# DM3370_Power.net
KiCad netlist of a schematic drawn in Altium Designer
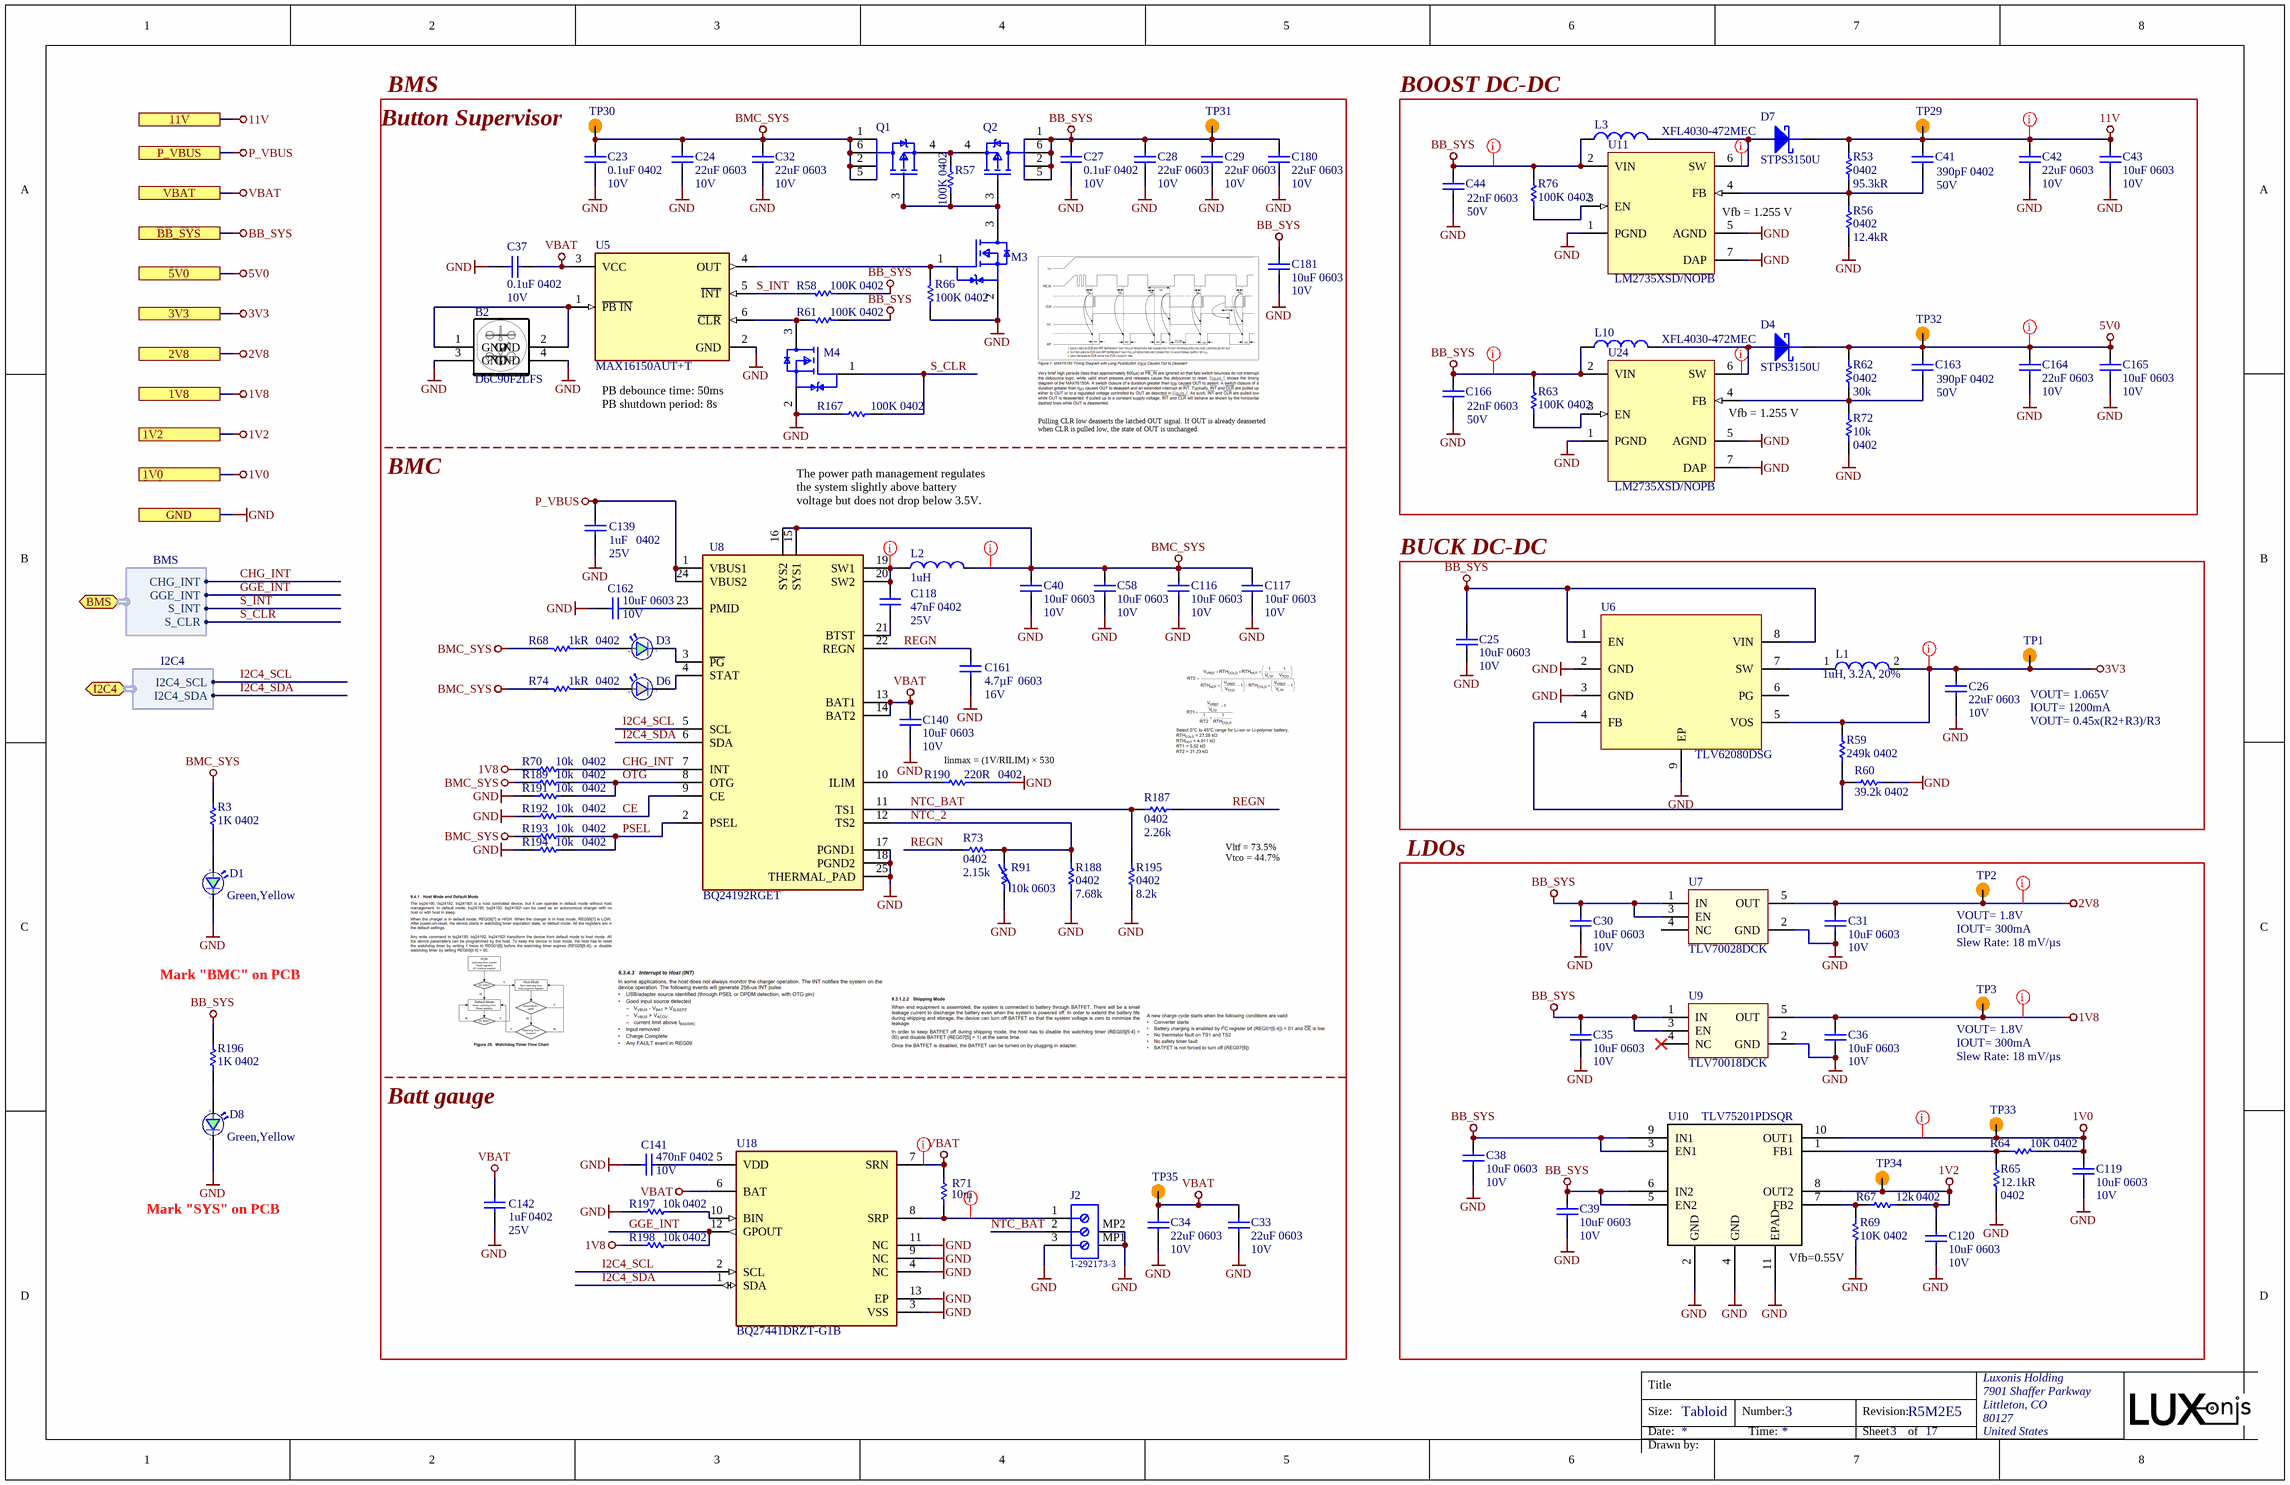
[diagram p0: DM3370_Power.SchDoc]

(export (version "E")
  (design (tool "Eeschema 10.0.6"))
  (components
    (comp (ref "B2")
      (value "D6C90F2LFS")
      (footprint "CON_B_BW2099_SoM_DF40HC-3.0-100DS-0.4V_minpad")
      (libsource (lib "Luxonis LLC") (part "D6C90"))
    )
    (comp (ref "C23")
      (value "0.1uF 0402")
      (footprint "CAP_Altium_Vault_Generic:CAPC0402(1005)70_L")
      (description "CAP CER 0.1UF 10V X7R 0402 5%")
      (fields (field (name "TOLERANCE") "5%") (field (name "VOLTAGE RATING") "10V"))
      (libsource (lib "LuxonisMaster") (part "GRM155R71A104JA01D"))
    )
    (comp (ref "C24")
      (value "22uF 0603")
      (footprint "CAP_Altium_Vault_Generic:CAPC0603(1608)100_L")
      (description "CAP CER 22UF 10V X5R 0603 20%")
      (fields (field (name "TOLERANCE") "20%") (field (name "VOLTAGE RATING") "10V"))
      (libsource (lib "LuxonisMaster") (part "GRM188R61A226ME15D"))
    )
    (comp (ref "C25")
      (value "10uF 0603")
      (footprint "CAP_Altium_Vault_Generic:CAPC0603(1608)100_L")
      (description "CAP CER 10UF 10V X5R 0603 20%")
      (fields (field (name "TOLERANCE") "20%") (field (name "VOLTAGE RATING") "10V"))
      (libsource (lib "LuxonisMaster") (part "GRM188R61A106ME69D"))
    )
    (comp (ref "C26")
      (value "22uF 0603")
      (footprint "CAP_Altium_Vault_Generic:CAPC0603(1608)100_L")
      (description "CAP CER 22UF 10V X5R 0603 20%")
      (fields (field (name "TOLERANCE") "20%") (field (name "VOLTAGE RATING") "10V"))
      (libsource (lib "LuxonisMaster") (part "GRM188R61A226ME15D"))
    )
    (comp (ref "C27")
      (value "0.1uF 0402")
      (footprint "CAP_Altium_Vault_Generic:CAPC0402(1005)70_L")
      (description "CAP CER 0.1UF 10V X7R 0402 5%")
      (fields (field (name "TOLERANCE") "5%") (field (name "VOLTAGE RATING") "10V"))
      (libsource (lib "LuxonisMaster") (part "GRM155R71A104JA01D"))
    )
    (comp (ref "C28")
      (value "22uF 0603")
      (footprint "CAP_Altium_Vault_Generic:CAPC0603(1608)100_L")
      (description "CAP CER 22UF 10V X5R 0603 20%")
      (fields (field (name "TOLERANCE") "20%") (field (name "VOLTAGE RATING") "10V"))
      (libsource (lib "LuxonisMaster") (part "GRM188R61A226ME15D"))
    )
    (comp (ref "C29")
      (value "22uF 0603")
      (footprint "CAP_Altium_Vault_Generic:CAPC0603(1608)100_L")
      (description "CAP CER 22UF 10V X5R 0603 20%")
      (fields (field (name "TOLERANCE") "20%") (field (name "VOLTAGE RATING") "10V"))
      (libsource (lib "LuxonisMaster") (part "GRM188R61A226ME15D"))
    )
    (comp (ref "C30")
      (value "10uF 0603")
      (footprint "CAP_Altium_Vault_Generic:CAPC0603(1608)100_L")
      (description "CAP CER 10UF 10V X5R 0603 20%")
      (fields (field (name "TOLERANCE") "20%") (field (name "VOLTAGE RATING") "10V"))
      (libsource (lib "LuxonisMaster") (part "GRM188R61A106ME69D"))
    )
    (comp (ref "C31")
      (value "10uF 0603")
      (footprint "CAP_Altium_Vault_Generic:CAPC0603(1608)100_L")
      (description "CAP CER 10UF 10V X5R 0603 20%")
      (fields (field (name "TOLERANCE") "20%") (field (name "VOLTAGE RATING") "10V"))
      (libsource (lib "LuxonisMaster") (part "GRM188R61A106ME69D"))
    )
    (comp (ref "C32")
      (value "22uF 0603")
      (footprint "CAP_Altium_Vault_Generic:CAPC0603(1608)100_L")
      (description "CAP CER 22UF 10V X5R 0603 20%")
      (fields (field (name "TOLERANCE") "20%") (field (name "VOLTAGE RATING") "10V"))
      (libsource (lib "LuxonisMaster") (part "GRM188R61A226ME15D"))
    )
    (comp (ref "C33")
      (value "22uF 0603")
      (footprint "CAP_Altium_Vault_Generic:CAPC0603(1608)100_L")
      (description "CAP CER 22UF 10V X5R 0603 20%")
      (fields (field (name "TOLERANCE") "20%") (field (name "VOLTAGE RATING") "10V"))
      (libsource (lib "LuxonisMaster") (part "GRM188R61A226ME15D"))
    )
    (comp (ref "C34")
      (value "22uF 0603")
      (footprint "CAP_Altium_Vault_Generic:CAPC0603(1608)100_L")
      (description "CAP CER 22UF 10V X5R 0603 20%")
      (fields (field (name "TOLERANCE") "20%") (field (name "VOLTAGE RATING") "10V"))
      (libsource (lib "LuxonisMaster") (part "GRM188R61A226ME15D"))
    )
    (comp (ref "C35")
      (value "10uF 0603")
      (footprint "CAP_Altium_Vault_Generic:CAPC0603(1608)100_L")
      (description "CAP CER 10UF 10V X5R 0603 20%")
      (fields (field (name "TOLERANCE") "20%") (field (name "VOLTAGE RATING") "10V"))
      (libsource (lib "LuxonisMaster") (part "GRM188R61A106ME69D"))
    )
    (comp (ref "C36")
      (value "10uF 0603")
      (footprint "CAP_Altium_Vault_Generic:CAPC0603(1608)100_L")
      (description "CAP CER 10UF 10V X5R 0603 20%")
      (fields (field (name "TOLERANCE") "20%") (field (name "VOLTAGE RATING") "10V"))
      (libsource (lib "LuxonisMaster") (part "GRM188R61A106ME69D"))
    )
    (comp (ref "C37")
      (value "0.1uF 0402")
      (footprint "CAP_Altium_Vault_Generic:CAPC0402(1005)70_L")
      (description "CAP CER 0.1UF 10V X7R 0402 5%")
      (fields (field (name "TOLERANCE") "5%") (field (name "VOLTAGE RATING") "10V"))
      (libsource (lib "LuxonisMaster") (part "GRM155R71A104JA01D"))
    )
    (comp (ref "C38")
      (value "10uF 0603")
      (footprint "CAP_Altium_Vault_Generic:CAPC0603(1608)100_L")
      (description "CAP CER 10UF 10V X5R 0603 20%")
      (fields (field (name "TOLERANCE") "20%") (field (name "VOLTAGE RATING") "10V"))
      (libsource (lib "LuxonisMaster") (part "GRM188R61A106ME69D"))
    )
    (comp (ref "C39")
      (value "10uF 0603")
      (footprint "CAP_Altium_Vault_Generic:CAPC0603(1608)100_L")
      (description "CAP CER 10UF 10V X5R 0603 20%")
      (fields (field (name "TOLERANCE") "20%") (field (name "VOLTAGE RATING") "10V"))
      (libsource (lib "LuxonisMaster") (part "GRM188R61A106ME69D"))
    )
    (comp (ref "C40")
      (value "10uF 0603")
      (footprint "CAP_Altium_Vault_Generic:CAPC0603(1608)100_L")
      (description "CAP CER 10UF 10V X5R 0603 20%")
      (fields (field (name "TOLERANCE") "20%") (field (name "VOLTAGE RATING") "10V"))
      (libsource (lib "LuxonisMaster") (part "GRM188R61A106ME69D"))
    )
    (comp (ref "C41")
      (value "GRM1555C1H391JA01J")
      (footprint "CAPC0402(1005)60_L")
      (description "CAP CER 390PF 50V C0G 0402")
      (fields
        (field (name "RATED DC VOLTAGE (URDC)") "50V")
        (field (name "CAPACITANCE") "390pF")
        (field (name "SIZE CODE") "0402")
      )
      (libsource (lib "Luxonis LLC") (part "LLL153C70G474ME17E"))
    )
    (comp (ref "C42")
      (value "22uF 0603")
      (footprint "CAP_Altium_Vault_Generic:CAPC0603(1608)100_L")
      (description "CAP CER 22UF 10V X5R 0603 20%")
      (fields (field (name "TOLERANCE") "20%") (field (name "VOLTAGE RATING") "10V"))
      (libsource (lib "LuxonisMaster") (part "GRM188R61A226ME15D"))
    )
    (comp (ref "C43")
      (value "10uF 0603")
      (footprint "CAP_Altium_Vault_Generic:CAPC0603(1608)100_L")
      (description "CAP CER 10UF 10V X5R 0603 20%")
      (fields (field (name "TOLERANCE") "20%") (field (name "VOLTAGE RATING") "10V"))
      (libsource (lib "LuxonisMaster") (part "GRM188R61A106ME69D"))
    )
    (comp (ref "C44")
      (value "C0603C223K5RACTU")
      (footprint "CAPC0603(1608)100_L")
      (description "CAP CER 0.022UF 50V X7R 0603")
      (fields
        (field (name "VOLTAGE RATING") "50V")
        (field (name "TOLERANCE") "10%")
        (field (name "CASE CODE (IMPERIAL)") "0603")
        (field (name "VOLTAGE") "50V")
        (field (name "CAPACITANCE") "22nF")
      )
      (libsource (lib "Luxonis LLC") (part "LLL153C70G474ME17E"))
    )
    (comp (ref "C58")
      (value "10uF 0603")
      (footprint "CAP_Altium_Vault_Generic:CAPC0603(1608)100_L")
      (description "CAP CER 10UF 10V X5R 0603 20%")
      (fields (field (name "TOLERANCE") "20%") (field (name "VOLTAGE RATING") "10V"))
      (libsource (lib "LuxonisMaster") (part "GRM188R61A106ME69D"))
    )
    (comp (ref "C116")
      (value "10uF 0603")
      (footprint "CAP_Altium_Vault_Generic:CAPC0603(1608)100_L")
      (description "CAP CER 10UF 10V X5R 0603 20%")
      (fields (field (name "TOLERANCE") "20%") (field (name "VOLTAGE RATING") "10V"))
      (libsource (lib "LuxonisMaster") (part "GRM188R61A106ME69D"))
    )
    (comp (ref "C117")
      (value "10uF 0603")
      (footprint "CAP_Altium_Vault_Generic:CAPC0603(1608)100_L")
      (description "CAP CER 10UF 10V X5R 0603 20%")
      (fields (field (name "TOLERANCE") "20%") (field (name "VOLTAGE RATING") "10V"))
      (libsource (lib "LuxonisMaster") (part "GRM188R61A106ME69D"))
    )
    (comp (ref "C118")
      (value "GRM155R71E473KA88D")
      (footprint "CAPC0402(1005)70_L")
      (description "CAP CER 0.047UF 25V X7R 0402 10%")
      (fields
        (field (name "CASE CODE (IMPERIAL)") "0402")
        (field (name "MANUFACTURER") "Murata")
        (field (name "CAPACITANCE") "47nF")
        (field (name "TOLERANCE") "10%")
        (field (name "VOLTAGE") "25V")
      )
      (libsource (lib "Luxonis LLC") (part "LLL153C70G474ME17E"))
    )
    (comp (ref "C119")
      (value "10uF 0603")
      (footprint "CAP_Altium_Vault_Generic:CAPC0603(1608)100_L")
      (description "CAP CER 10UF 10V X5R 0603 20%")
      (fields (field (name "TOLERANCE") "20%") (field (name "VOLTAGE RATING") "10V"))
      (libsource (lib "LuxonisMaster") (part "GRM188R61A106ME69D"))
    )
    (comp (ref "C120")
      (value "10uF 0603")
      (footprint "CAP_Altium_Vault_Generic:CAPC0603(1608)100_L")
      (description "CAP CER 10UF 10V X5R 0603 20%")
      (fields (field (name "TOLERANCE") "20%") (field (name "VOLTAGE RATING") "10V"))
      (libsource (lib "LuxonisMaster") (part "GRM188R61A106ME69D"))
    )
    (comp (ref "C139")
      (value "GRM155R61E105KA12D")
      (footprint "CAPC0402(1005)70_L")
      (description "CAP CER 1UF 25V X5R 0402 10%")
      (fields
        (field (name "CASE CODE (IMPERIAL)") "0402")
        (field (name "VOLTAGE") "25V")
        (field (name "CAPACITANCE") "1uF")
        (field (name "TOLERANCE") "10%")
      )
      (libsource (lib "Luxonis LLC") (part "GRM188R61C475KAAJD"))
    )
    (comp (ref "C140")
      (value "10uF 0603")
      (footprint "CAP_Altium_Vault_Generic:CAPC0603(1608)100_L")
      (description "CAP CER 10UF 10V X5R 0603 20%")
      (fields (field (name "TOLERANCE") "20%") (field (name "VOLTAGE RATING") "10V"))
      (libsource (lib "LuxonisMaster") (part "GRM188R61A106ME69D"))
    )
    (comp (ref "C141")
      (value "GRM155R61A474KE15D")
      (footprint "CAPC0402(1005)70_L")
      (description "CAP CER 0.47UF 10V X5R 0402")
      (fields
        (field (name "VOLTAGE RATING") "10V")
        (field (name "CAPACITANCE") "470nF")
        (field (name "TOLERANCE") "10%")
        (field (name "CASE/PACKAGE") "0402")
        (field (name "VOLTAGE") "10V")
      )
      (libsource (lib "Luxonis LLC") (part "LLL153C70G474ME17E"))
    )
    (comp (ref "C142")
      (value "GRM155R61E105KA12D")
      (footprint "CAPC0402(1005)70_L")
      (description "CAP CER 1UF 25V X5R 0402 10%")
      (fields
        (field (name "CASE CODE (IMPERIAL)") "0402")
        (field (name "VOLTAGE") "25V")
        (field (name "CAPACITANCE") "1uF")
        (field (name "TOLERANCE") "10%")
      )
      (libsource (lib "Luxonis LLC") (part "GRM188R61C475KAAJD"))
    )
    (comp (ref "C161")
      (value "4.7µF")
      (footprint "CAPC0603(1608)100_L")
      (description "CAP CER 4.7UF 16V X5R 0603 10%")
      (fields
        (field (name "VOLTAGE RATING") "16V")
        (field (name "TOLERANCE") "10%")
        (field (name "CASE/PACKAGE") "0603")
        (field (name "Comment") "GRM188R61C475KAAJD")
      )
      (libsource (lib "Luxonis LLC") (part "LLL153C70G474ME17E"))
    )
    (comp (ref "C162")
      (value "10uF 0603")
      (footprint "CAP_Altium_Vault_Generic:CAPC0603(1608)100_L")
      (description "CAP CER 10UF 10V X5R 0603 20%")
      (fields (field (name "TOLERANCE") "20%") (field (name "VOLTAGE RATING") "10V"))
      (libsource (lib "LuxonisMaster") (part "GRM188R61A106ME69D"))
    )
    (comp (ref "C163")
      (value "GRM1555C1H391JA01J")
      (footprint "CAPC0402(1005)60_L")
      (description "CAP CER 390PF 50V C0G 0402")
      (fields
        (field (name "RATED DC VOLTAGE (URDC)") "50V")
        (field (name "CAPACITANCE") "390pF")
        (field (name "SIZE CODE") "0402")
      )
      (libsource (lib "Luxonis LLC") (part "LLL153C70G474ME17E"))
    )
    (comp (ref "C164")
      (value "22uF 0603")
      (footprint "CAP_Altium_Vault_Generic:CAPC0603(1608)100_L")
      (description "CAP CER 22UF 10V X5R 0603 20%")
      (fields (field (name "TOLERANCE") "20%") (field (name "VOLTAGE RATING") "10V"))
      (libsource (lib "LuxonisMaster") (part "GRM188R61A226ME15D"))
    )
    (comp (ref "C165")
      (value "10uF 0603")
      (footprint "CAP_Altium_Vault_Generic:CAPC0603(1608)100_L")
      (description "CAP CER 10UF 10V X5R 0603 20%")
      (fields (field (name "TOLERANCE") "20%") (field (name "VOLTAGE RATING") "10V"))
      (libsource (lib "LuxonisMaster") (part "GRM188R61A106ME69D"))
    )
    (comp (ref "C166")
      (value "C0603C223K5RACTU")
      (footprint "CAPC0603(1608)100_L")
      (description "CAP CER 0.022UF 50V X7R 0603")
      (fields
        (field (name "VOLTAGE RATING") "50V")
        (field (name "TOLERANCE") "10%")
        (field (name "CASE CODE (IMPERIAL)") "0603")
        (field (name "VOLTAGE") "50V")
        (field (name "CAPACITANCE") "22nF")
      )
      (libsource (lib "Luxonis LLC") (part "LLL153C70G474ME17E"))
    )
    (comp (ref "C180")
      (value "22uF 0603")
      (footprint "CAP_Altium_Vault_Generic:CAPC0603(1608)100_L")
      (description "CAP CER 22UF 10V X5R 0603 20%")
      (fields (field (name "TOLERANCE") "20%") (field (name "VOLTAGE RATING") "10V"))
      (libsource (lib "LuxonisMaster") (part "GRM188R61A226ME15D"))
    )
    (comp (ref "C181")
      (value "10uF 0603")
      (footprint "CAP_Altium_Vault_Generic:CAPC0603(1608)100_L")
      (description "CAP CER 10UF 10V X5R 0603 20%")
      (fields (field (name "TOLERANCE") "20%") (field (name "VOLTAGE RATING") "10V"))
      (libsource (lib "LuxonisMaster") (part "GRM188R61A106ME69D"))
    )
    (comp (ref "D1")
      (value "SML-D12M8WT86")
      (footprint "SML_D1xx8W")
      (description "LED GREEN DIFFUSED 0603 SMD Green 572nm LED Indication - Discrete 2.2V 0603 (1608 Metric)")
      (fields (field (name "COLOR") "Green,Yellow"))
      (libsource (lib "Luxonis LLC") (part "SML-D12M8WT86"))
    )
    (comp (ref "D3")
      (value "SML-D12M8WT86")
      (footprint "SML_D1xx8W")
      (description "LED GREEN DIFFUSED 0603 SMD Green 572nm LED Indication - Discrete 2.2V 0603 (1608 Metric)")
      (fields (field (name "MANUFACTURER") "Rohm"))
      (libsource (lib "Luxonis LLC") (part "SML-D12M8WT86"))
    )
    (comp (ref "D4")
      (value "STPS3150U")
      (footprint "FP-SMB-MFG")
      (description "DIODE SCHOTTKY 150V 3A SMB")
      (fields
        (field (name "OCTOPART") "https://octopart.com/stps3150u-stmicroelectronics-39552976")
        (field (name "MANUFACTURER") "STMicroelectronics")
      )
      (libsource (lib "LuxonisMaster") (part "STPS3150U"))
    )
    (comp (ref "D6")
      (value "SML-D12D8WT86")
      (footprint "SML_D1xx8W")
      (description "LED ORANGE DIFFUSED 0603 SMD Orange 605nm LED Indication - Discrete 2.2V 0603 (1608 Metric)")
      (libsource (lib "Luxonis LLC") (part "SML-D12D8WT86"))
    )
    (comp (ref "D7")
      (value "STPS3150U")
      (footprint "FP-SMB-MFG")
      (description "DIODE SCHOTTKY 150V 3A SMB")
      (fields
        (field (name "OCTOPART") "https://octopart.com/stps3150u-stmicroelectronics-39552976")
        (field (name "MANUFACTURER") "STMicroelectronics")
      )
      (libsource (lib "LuxonisMaster") (part "STPS3150U"))
    )
    (comp (ref "D8")
      (value "SML-D12M8WT86")
      (footprint "SML_D1xx8W")
      (description "LED GREEN DIFFUSED 0603 SMD Green 572nm LED Indication - Discrete 2.2V 0603 (1608 Metric)")
      (fields (field (name "COLOR") "Green,Yellow"))
      (libsource (lib "Luxonis LLC") (part "SML-D12M8WT86"))
    )
    (comp (ref "J2")
      (value "1-292173-3")
      (footprint "1-292173-3")
      (description "Board Connector, 3 Contact(s), 1 Row(s), Male, Right Angle, Surface Mount Terminal")
      (libsource (lib "Luxonis LLC") (part "1-292173-3"))
    )
    (comp (ref "L1")
      (value "1uH, 3.2A, 20%")
      (footprint "LuxonisMaster:DFE252012P-1R0M=P2")
      (description "FIXED IND 1UH 3.2A 42 MOHM SMD")
      (fields
        (field (name "MANUFACTURER") "Murata")
        (field (name "MANUFACTURER PART NUMBER") "DFE252012P-1R0M=P2")
      )
      (libsource (lib "LuxonisMaster") (part "DFE252012P-1R0M=P2"))
    )
    (comp (ref "L2")
      (value "XFL4020-102MEC")
      (footprint "COIL-XFL4020_V")
      (description "Fixed Inductors 11A 11.9mR XFL4020")
      (fields
        (field (name "TOLERANCE") "20%")
        (field (name "INDUCTANCE") "1uH")
        (field (name "AVAILABLE PREVIEW IMAGES") "2D")
      )
      (libsource (lib "Luxonis LLC") (part "XFL4030-472MEC"))
    )
    (comp (ref "L3")
      (value "XFL4030-472MEC")
      (footprint "XFL4030-472MEC-MFG")
      (description "Fixed Inductors 5.7A 25mR XFL4030")
      (libsource (lib "LuxonisMaster") (part "XFL4030-472MEC"))
    )
    (comp (ref "L10")
      (value "XFL4030-472MEC")
      (footprint "XFL4030-472MEC-MFG")
      (description "Fixed Inductors 5.7A 25mR XFL4030")
      (libsource (lib "LuxonisMaster") (part "XFL4030-472MEC"))
    )
    (comp (ref "M3")
      (value "RE1C002UNTCL")
      (footprint "LuxonisMaster:RE1C002UNTCL")
      (description "MOSFET N-CH 20V 0.2A EMT3")
      (libsource (lib "LuxonisMaster") (part "RE1C002UNTCL"))
    )
    (comp (ref "M4")
      (value "RE1C002UNTCL")
      (footprint "LuxonisMaster:RE1C002UNTCL")
      (description "MOSFET N-CH 20V 0.2A EMT3")
      (libsource (lib "LuxonisMaster") (part "RE1C002UNTCL"))
    )
    (comp (ref "Q1")
      (value "IRLTS2242TRPBF")
      (footprint "TSOP-6-MFG")
      (description "MOSFET P-CH 20V 6.9A 6TSOP")
      (libsource (lib "Luxonis LLC") (part "IRLTS2242TRPBF"))
    )
    (comp (ref "Q2")
      (value "IRLTS2242TRPBF")
      (footprint "TSOP-6-MFG")
      (description "MOSFET P-CH 20V 6.9A 6TSOP")
      (libsource (lib "Luxonis LLC") (part "IRLTS2242TRPBF"))
    )
    (comp (ref "R3")
      (value "1K 0402")
      (footprint "RES_Altium_Vault_Generic:RESC0402(1005)_L")
      (fields (field (name "TOLERANCE") "1%"))
      (libsource (lib "LuxonisMaster") (part "RC0402FR-071KL"))
    )
    (comp (ref "R53")
      (value "CRCW040295K3FKED")
      (footprint "RESC0402(1005)_L")
      (description "RES SMD 95.3K OHM 1% 1/16W 0402")
      (fields
        (field (name "CASE CODE (IMPERIAL)") "0402")
        (field (name "RESISTANCE") "95.3kR")
        (field (name "TOLERANCE") "1%")
      )
      (libsource (lib "Luxonis LLC") (part "CR0402-FX-2492GLF"))
    )
    (comp (ref "R56")
      (value "RC0402FR-0712K4L")
      (footprint "RESC0402(1005)_L")
      (description "RES SMD 12.4K OHM 1% 1/16W 0402")
      (fields
        (field (name "CASE CODE (IMPERIAL)") "0402")
        (field (name "TOLERANCE") "1%")
        (field (name "RESISTANCE") "12.4kR")
      )
      (libsource (lib "Luxonis LLC") (part "CR0402-FX-2492GLF"))
    )
    (comp (ref "R57")
      (value "100K 0402")
      (footprint "RES_Altium_Vault_Generic:RESC0402(1005)_L")
      (description "RES SMD 100K OHM 1% 1/16W 0402")
      (fields (field (name "TOLERANCE") "1%"))
      (libsource (lib "LuxonisMaster") (part "RC0402FR-07100KL"))
    )
    (comp (ref "R58")
      (value "100K 0402")
      (footprint "RES_Altium_Vault_Generic:RESC0402(1005)_L")
      (description "RES SMD 100K OHM 1% 1/16W 0402")
      (fields (field (name "TOLERANCE") "1%"))
      (libsource (lib "LuxonisMaster") (part "RC0402FR-07100KL"))
    )
    (comp (ref "R59")
      (value "249k 0402")
      (footprint "RES_Altium_Vault_Generic:RESC0402(1005)_L")
      (description "RES SMD 249K OHM 1% 1/16W 0402")
      (fields (field (name "TOLERANCE") "1%"))
      (libsource (lib "LuxonisMaster") (part "CRCW0402249KFKED"))
    )
    (comp (ref "R60")
      (value "39.2k 0402")
      (footprint "RES_Altium_Vault_Generic:RESC0402(1005)_L")
      (description "RES SMD 39.2K OHM 1% 1/16W 0402")
      (fields (field (name "TOLERANCE") "1%"))
      (libsource (lib "LuxonisMaster") (part "CRCW040239K2FKED"))
    )
    (comp (ref "R61")
      (value "100K 0402")
      (footprint "RES_Altium_Vault_Generic:RESC0402(1005)_L")
      (description "RES SMD 100K OHM 1% 1/16W 0402")
      (fields (field (name "TOLERANCE") "1%"))
      (libsource (lib "LuxonisMaster") (part "RC0402FR-07100KL"))
    )
    (comp (ref "R62")
      (value "30k")
      (footprint "RESC0402(1005)_L")
      (description "RES SMD 30K OHM 1% 1/16W 0402")
      (fields
        (field (name "CASE/PACKAGE") "0402")
        (field (name "TOLERANCE") "1%")
        (field (name "Comment") "RC0402FR-0730KL")
      )
      (libsource (lib "Luxonis LLC") (part "Default resistor symbol"))
    )
    (comp (ref "R63")
      (value "100K 0402")
      (footprint "RES_Altium_Vault_Generic:RESC0402(1005)_L")
      (description "RES SMD 100K OHM 1% 1/16W 0402")
      (fields (field (name "TOLERANCE") "1%"))
      (libsource (lib "LuxonisMaster") (part "RC0402FR-07100KL"))
    )
    (comp (ref "R64")
      (value "10K 0402")
      (footprint "RES_Altium_Vault_Generic:RESC0402(1005)_L")
      (fields (field (name "TOLERANCE") "1%"))
      (libsource (lib "LuxonisMaster") (part "RC0402FR-1310KL"))
    )
    (comp (ref "R65")
      (value "RC0402FR-0712K1L")
      (footprint "RESC0402(1005)_L")
      (description "RES SMD 12.1K OHM 1% 1/16W 0402")
      (fields
        (field (name "RESISTANCE") "12.1kR")
        (field (name "SIZE CODE") "0402")
        (field (name "TOLERANCE") "1%")
      )
      (libsource (lib "Luxonis LLC") (part "CR1206-FX-10R0ELF"))
    )
    (comp (ref "R66")
      (value "100K 0402")
      (footprint "RES_Altium_Vault_Generic:RESC0402(1005)_L")
      (description "RES SMD 100K OHM 1% 1/16W 0402")
      (fields (field (name "TOLERANCE") "1%"))
      (libsource (lib "LuxonisMaster") (part "RC0402FR-07100KL"))
    )
    (comp (ref "R67")
      (value "12k")
      (footprint "RESC0402(1005)_L")
      (fields
        (field (name "CASE/PACKAGE") "0402")
        (field (name "TOLERANCE") "1%")
        (field (name "Comment") "RC0402FR-0712KL")
      )
      (libsource (lib "Luxonis LLC") (part "CR0402-FX-2492GLF"))
    )
    (comp (ref "R68")
      (value "RC0402FR-071KL")
      (footprint "RESC0402(1005)_L")
      (fields
        (field (name "CASE CODE (IMPERIAL)") "0402")
        (field (name "TOLERANCE") "1%")
        (field (name "RESISTANCE") "1kR")
      )
      (libsource (lib "Luxonis LLC") (part "CR0402-FX-2492GLF"))
    )
    (comp (ref "R69")
      (value "10K 0402")
      (footprint "RES_Altium_Vault_Generic:RESC0402(1005)_L")
      (fields (field (name "TOLERANCE") "1%"))
      (libsource (lib "LuxonisMaster") (part "RC0402FR-1310KL"))
    )
    (comp (ref "R70")
      (value "10k")
      (footprint "RESC0402(1005)_L")
      (fields
        (field (name "TOLERANCE") "1%")
        (field (name "CASE/PACKAGE") "0402")
        (field (name "Comment") "RC0402FR-1310KL")
      )
      (libsource (lib "Luxonis LLC") (part "RC0402FR-0722RL_1"))
    )
    (comp (ref "R71")
      (value "10m")
      (footprint "RESC0805(2012)_M")
      (description "RES SMD 0805 10mOhm 1% 1/4W")
      (fields (field (name "TOLERANCE") "1%") (field (name "Comment") "ERJ-6BWFR010V"))
      (libsource (lib "Luxonis LLC") (part "Default resistor symbol"))
    )
    (comp (ref "R72")
      (value "10k")
      (footprint "RESC0402(1005)_L")
      (fields
        (field (name "TOLERANCE") "1%")
        (field (name "CASE/PACKAGE") "0402")
        (field (name "Comment") "RC0402FR-1310KL")
      )
      (libsource (lib "Luxonis LLC") (part "RC0402FR-0722RL_1"))
    )
    (comp (ref "R73")
      (value "2.15k")
      (footprint "RESC0402(1005)_L")
      (description "RES SMD 2.15k OHM 1% 1/16W")
      (fields
        (field (name "CASE/PACKAGE") "0402")
        (field (name "TOLERANCE") "1%")
        (field (name "Comment") "CRCW04022K15FKED")
      )
      (libsource (lib "Luxonis LLC") (part "Default resistor symbol"))
    )
    (comp (ref "R74")
      (value "RC0402FR-071KL")
      (footprint "RESC0402(1005)_L")
      (fields
        (field (name "CASE CODE (IMPERIAL)") "0402")
        (field (name "TOLERANCE") "1%")
        (field (name "RESISTANCE") "1kR")
      )
      (libsource (lib "Luxonis LLC") (part "CR0402-FX-2492GLF"))
    )
    (comp (ref "R76")
      (value "100K 0402")
      (footprint "RES_Altium_Vault_Generic:RESC0402(1005)_L")
      (description "RES SMD 100K OHM 1% 1/16W 0402")
      (fields (field (name "TOLERANCE") "1%"))
      (libsource (lib "LuxonisMaster") (part "RC0402FR-07100KL"))
    )
    (comp (ref "R91")
      (value "10k")
      (footprint "RESC0603(1608)_N")
      (description "NTC Thermistor, 10000ohm, Surface Mount")
      (fields
        (field (name "TOLERANCE") "1%")
        (field (name "CASE/PACKAGE") "0603")
        (field (name "Comment") "NTCG163JF103FT1")
      )
      (libsource (lib "Luxonis LLC") (part "NTCG163JF103FT1"))
    )
    (comp (ref "R167")
      (value "100K 0402")
      (footprint "RES_Altium_Vault_Generic:RESC0402(1005)_L")
      (description "RES SMD 100K OHM 1% 1/16W 0402")
      (fields (field (name "TOLERANCE") "1%"))
      (libsource (lib "LuxonisMaster") (part "RC0402FR-07100KL"))
    )
    (comp (ref "R187")
      (value "2.26k")
      (footprint "RESC0402(1005)_L")
      (description "RES SMD 2.26K OHM 1% 1/16W 0402")
      (fields
        (field (name "CASE/PACKAGE") "0402")
        (field (name "TOLERANCE") "1%")
        (field (name "Comment") "CRCW04022K26FKED")
      )
      (libsource (lib "Luxonis LLC") (part "Default resistor symbol"))
    )
    (comp (ref "R188")
      (value "7.68k")
      (footprint "RESC0402(1005)_L")
      (description "RES SMD 7.68K OHM 1% 1/16W 0402")
      (fields
        (field (name "CASE/PACKAGE") "0402")
        (field (name "TOLERANCE") "1%")
        (field (name "Comment") "CRCW04027K68FKTD")
      )
      (libsource (lib "Luxonis LLC") (part "Default resistor symbol"))
    )
    (comp (ref "R189")
      (value "10k")
      (footprint "RESC0402(1005)_L")
      (fields
        (field (name "TOLERANCE") "1%")
        (field (name "CASE/PACKAGE") "0402")
        (field (name "Comment") "RC0402FR-1310KL")
      )
      (libsource (lib "Luxonis LLC") (part "RC0402FR-0722RL_1"))
    )
    (comp (ref "R190")
      (value "RC0402FR-07220RL")
      (footprint "RESC0402(1005)_L")
      (description "RES SMD 220 OHM 1% 1/16W 0402")
      (fields
        (field (name "TOLERANCE") "1%")
        (field (name "RESISTANCE") "220R")
        (field (name "CASE CODE (IMPERIAL)") "0402")
      )
      (libsource (lib "Luxonis LLC") (part "CR0402-FX-2492GLF"))
    )
    (comp (ref "R191")
      (value "10k")
      (footprint "RESC0402(1005)_L")
      (fields
        (field (name "TOLERANCE") "1%")
        (field (name "CASE/PACKAGE") "0402")
        (field (name "Comment") "RC0402FR-1310KL")
      )
      (libsource (lib "Luxonis LLC") (part "RC0402FR-0722RL_1"))
    )
    (comp (ref "R192")
      (value "10k")
      (footprint "RESC0402(1005)_L")
      (fields
        (field (name "TOLERANCE") "1%")
        (field (name "CASE/PACKAGE") "0402")
        (field (name "Comment") "RC0402FR-1310KL")
      )
      (libsource (lib "Luxonis LLC") (part "RC0402FR-0722RL_1"))
    )
    (comp (ref "R193")
      (value "10k")
      (footprint "RESC0402(1005)_L")
      (fields
        (field (name "TOLERANCE") "1%")
        (field (name "CASE/PACKAGE") "0402")
        (field (name "Comment") "RC0402FR-1310KL")
      )
      (libsource (lib "Luxonis LLC") (part "RC0402FR-0722RL_1"))
    )
    (comp (ref "R194")
      (value "10k")
      (footprint "RESC0402(1005)_L")
      (fields
        (field (name "TOLERANCE") "1%")
        (field (name "CASE/PACKAGE") "0402")
        (field (name "Comment") "RC0402FR-1310KL")
      )
      (libsource (lib "Luxonis LLC") (part "RC0402FR-0722RL_1"))
    )
    (comp (ref "R195")
      (value "8.2k")
      (footprint "RESC0402(1005)_L")
      (description "RES SMD 8.2K OHM 1% 1/16W 0402")
      (fields
        (field (name "CASE/PACKAGE") "0402")
        (field (name "TOLERANCE") "1%")
        (field (name "Comment") "CR0402-FX-8201GLF")
      )
      (libsource (lib "Luxonis LLC") (part "Default resistor symbol"))
    )
    (comp (ref "R196")
      (value "1K 0402")
      (footprint "RES_Altium_Vault_Generic:RESC0402(1005)_L")
      (fields (field (name "TOLERANCE") "1%"))
      (libsource (lib "LuxonisMaster") (part "RC0402FR-071KL"))
    )
    (comp (ref "R197")
      (value "10k")
      (footprint "RESC0402(1005)_L")
      (fields
        (field (name "TOLERANCE") "1%")
        (field (name "CASE/PACKAGE") "0402")
        (field (name "Comment") "RC0402FR-1310KL")
      )
      (libsource (lib "Luxonis LLC") (part "RC0402FR-0722RL_1"))
    )
    (comp (ref "R198")
      (value "10k")
      (footprint "RESC0402(1005)_L")
      (fields
        (field (name "TOLERANCE") "1%")
        (field (name "CASE/PACKAGE") "0402")
        (field (name "Comment") "RC0402FR-1310KL")
      )
      (libsource (lib "Luxonis LLC") (part "RC0402FR-0722RL_1"))
    )
    (comp (ref "TP1")
      (value "TP100_200_NS")
      (footprint "LuxonisMaster:TP100_200_NS")
      (libsource (lib "LuxonisMaster") (part "TEST_POINT"))
    )
    (comp (ref "TP2")
      (value "TP100_200_NS")
      (footprint "LuxonisMaster:TP100_200_NS")
      (libsource (lib "LuxonisMaster") (part "TEST_POINT"))
    )
    (comp (ref "TP3")
      (value "TP100_200_NS")
      (footprint "LuxonisMaster:TP100_200_NS")
      (libsource (lib "LuxonisMaster") (part "TEST_POINT"))
    )
    (comp (ref "TP29")
      (value "TP100_200_NS")
      (footprint "LuxonisMaster:TP100_200_NS")
      (libsource (lib "LuxonisMaster") (part "TEST_POINT"))
    )
    (comp (ref "TP30")
      (value "TP100_200_NS")
      (footprint "LuxonisMaster:TP100_200_NS")
      (libsource (lib "LuxonisMaster") (part "TEST_POINT"))
    )
    (comp (ref "TP31")
      (value "TP100_200_NS")
      (footprint "LuxonisMaster:TP100_200_NS")
      (libsource (lib "LuxonisMaster") (part "TEST_POINT"))
    )
    (comp (ref "TP32")
      (value "TP100_200_NS")
      (footprint "LuxonisMaster:TP100_200_NS")
      (libsource (lib "LuxonisMaster") (part "TEST_POINT"))
    )
    (comp (ref "TP33")
      (value "TP100_200_NS")
      (footprint "LuxonisMaster:TP100_200_NS")
      (libsource (lib "LuxonisMaster") (part "TEST_POINT"))
    )
    (comp (ref "TP34")
      (value "TP100_200_NS")
      (footprint "LuxonisMaster:TP100_200_NS")
      (libsource (lib "LuxonisMaster") (part "TEST_POINT"))
    )
    (comp (ref "TP35")
      (value "TP100_200_NS")
      (footprint "LuxonisMaster:TP100_200_NS")
      (libsource (lib "LuxonisMaster") (part "TEST_POINT"))
    )
    (comp (ref "U5")
      (value "MAX16150AUT+T")
      (footprint "FP-U6-1-MFG")
      (description "Power Supply Support Circuit, Fixed, 1 Channel, PDSO6")
      (libsource (lib "Luxonis LLC") (part "36a392858d03d148bb8ce7f45f4b5f9"))
    )
    (comp (ref "U6")
      (value "TLV62080DSG")
      (footprint "LuxonisMaster:TLV62080DSG")
      (description "IC REG BUCK ADJ 1.2A SYNC 8WSON")
      (libsource (lib "LuxonisMaster") (part "TLV62080DSG"))
    )
    (comp (ref "U7")
      (value "TLV70028DCK")
      (footprint "TLV70028DCK")
      (description "IC REG LINEAR 2.8V 200MA SC70-5 Linear Voltage Regulator IC  1 Output  200mA SC-70-5")
      (libsource (lib "Luxonis LLC") (part "TLV70028DCK"))
    )
    (comp (ref "U8")
      (value "BQ24192RGET")
      (footprint "BQ24192IRGET-Footprint-1")
      (description "Power Supply Management Circuit, Fixed, 1 Channel, +18V, PQCC24")
      (libsource (lib "Luxonis LLC") (part "BQ24192IRGET-Symbol-1"))
    )
    (comp (ref "U9")
      (value "TLV70018DCK")
      (footprint "LuxonisMaster:TLV70018DCK")
      (description "IC REG LINEAR 1.8V 200MA SC70-5 Linear Voltage Regulator IC  1 Output  200mA SC-70-5")
      (libsource (lib "LuxonisMaster") (part "TLV70018DCK"))
    )
    (comp (ref "U10")
      (value "TLV75201PDSQR")
      (footprint "SON_1PDSQR_TEX")
      (description "TLV752 Dual, 1-A, High-Accuracy, Adjustable-LDO in a Small-Size Package")
      (fields
        (field (name "MANUFACTURER PART NUMBER 1") "TLV75201PDSQR")
        (field (name "COPYRIGHT") "Copyright (C) 2021 Ultra Librarian. All rights reserved.")
      )
      (libsource (lib "Luxonis LLC") (part "TLV75201PDSQR"))
    )
    (comp (ref "U11")
      (value "LM2735XSD/NOPB")
      (footprint "NGG0006A_V")
      (description "520kHz/1.6MHz space efficient boost and SEPIC DC-DC regulator 6-WSON -40 to 125")
      (fields (field (name "MANUFACTURER PART NUMBER 1") "LM2735XSD/NOPB"))
      (libsource (lib "Luxonis LLC") (part "PM-DCDC-LM2735SD"))
    )
    (comp (ref "U18")
      (value "BQ27441DRZT-G1B")
      (footprint "FP-DRZ0012A-MFG")
      (description "Power Supply Management Circuit, Fixed, 1 Channel, PDSO12")
      (libsource (lib "Luxonis LLC") (part "BQ27441DRZT-G1B"))
    )
    (comp (ref "U24")
      (value "LM2735XSD/NOPB")
      (footprint "NGG0006A_V")
      (description "520kHz/1.6MHz space efficient boost and SEPIC DC-DC regulator 6-WSON -40 to 125")
      (fields (field (name "MANUFACTURER PART NUMBER 1") "LM2735XSD/NOPB"))
      (libsource (lib "Luxonis LLC") (part "PM-DCDC-LM2735SD"))
    )
  )
  (nets
    (net (code "3") (name "/CE") (class "Default")
      (node (ref "R192") (pin "2") (pinfunction "2_2") (pintype "passive"))
      (node (ref "U8") (pin "9") (pinfunction "CE_9") (pintype "passive"))
    )
    (net (code "4") (name "/CHG_INT") (class "Default")
      (node (ref "R70") (pin "2") (pinfunction "2_2") (pintype "passive"))
      (node (ref "U8") (pin "7") (pinfunction "INT_7") (pintype "passive"))
    )
    (net (code "5") (name "/GGE_INT") (class "Default")
      (node (ref "R198") (pin "2") (pinfunction "2_2") (pintype "passive"))
      (node (ref "U18") (pin "12") (pinfunction "GPOUT_12") (pintype "output"))
    )
    (net (code "6") (name "/I2C4_SCL") (class "Default")
      (node (ref "U18") (pin "2") (pinfunction "SCL_2") (pintype "input"))
      (node (ref "U8") (pin "5") (pinfunction "SCL_5") (pintype "passive"))
    )
    (net (code "7") (name "/I2C4_SDA") (class "Default")
      (node (ref "U18") (pin "1") (pinfunction "SDA_1") (pintype "bidirectional"))
      (node (ref "U8") (pin "6") (pinfunction "SDA_6") (pintype "passive"))
    )
    (net (code "8") (name "/NTC_2") (class "Default")
      (node (ref "R188") (pin "2") (pinfunction "2_2") (pintype "passive"))
      (node (ref "R73") (pin "2") (pinfunction "2_2") (pintype "passive"))
      (node (ref "R91") (pin "2") (pinfunction "2_2") (pintype "passive"))
      (node (ref "U8") (pin "12") (pinfunction "TS2_12") (pintype "passive"))
    )
    (net (code "9") (name "/NTC_BAT") (class "Default")
      (node (ref "J2") (pin "2") (pinfunction "2_2") (pintype "passive"))
      (node (ref "R187") (pin "1") (pinfunction "1_1") (pintype "passive"))
      (node (ref "R195") (pin "2") (pinfunction "2_2") (pintype "passive"))
      (node (ref "U8") (pin "11") (pinfunction "TS1_11") (pintype "passive"))
    )
    (net (code "10") (name "/OTG") (class "Default")
      (node (ref "R189") (pin "2") (pinfunction "2_2") (pintype "passive"))
      (node (ref "R191") (pin "2") (pinfunction "2_2") (pintype "passive"))
      (node (ref "U8") (pin "8") (pinfunction "OTG_8") (pintype "passive"))
    )
    (net (code "11") (name "/PSEL") (class "Default")
      (node (ref "R193") (pin "2") (pinfunction "2_2") (pintype "passive"))
      (node (ref "R194") (pin "2") (pinfunction "2_2") (pintype "passive"))
      (node (ref "U8") (pin "2") (pinfunction "PSEL_2") (pintype "passive"))
    )
    (net (code "12") (name "/REGN") (class "Default")
      (node (ref "C161") (pin "2") (pinfunction "2_2") (pintype "passive"))
      (node (ref "R187") (pin "2") (pinfunction "2_2") (pintype "passive"))
      (node (ref "R73") (pin "1") (pinfunction "1_1") (pintype "passive"))
      (node (ref "U8") (pin "22") (pinfunction "REGN_22") (pintype "passive"))
    )
    (net (code "13") (name "/S_CLR") (class "Default")
      (node (ref "M4") (pin "1") (pinfunction "Gate_1") (pintype "passive"))
      (node (ref "R167") (pin "2") (pinfunction "2_2") (pintype "passive"))
    )
    (net (code "14") (name "/S_INT") (class "Default")
      (node (ref "R58") (pin "1") (pinfunction "1_1") (pintype "passive"))
      (node (ref "U5") (pin "5") (pinfunction "~{INT}_5") (pintype "input"))
    )
    (net (code "17") (name "1V0") (class "Default")
      (node (ref "C119") (pin "2") (pinfunction "2_2") (pintype "passive"))
      (node (ref "R64") (pin "2") (pinfunction "2_2") (pintype "passive"))
      (node (ref "TP33") (pin "1") (pintype "passive"))
      (node (ref "U10") (pin "10") (pinfunction "OUT1_10") (pintype "passive"))
    )
    (net (code "18") (name "1V2") (class "Default")
      (node (ref "C120") (pin "2") (pinfunction "2_2") (pintype "passive"))
      (node (ref "R67") (pin "1") (pinfunction "1_1") (pintype "passive"))
      (node (ref "TP34") (pin "1") (pintype "passive"))
      (node (ref "U10") (pin "8") (pinfunction "OUT2_8") (pintype "passive"))
    )
    (net (code "19") (name "1V8") (class "Default")
      (node (ref "C36") (pin "2") (pinfunction "2_2") (pintype "passive"))
      (node (ref "R198") (pin "1") (pinfunction "1_1") (pintype "passive"))
      (node (ref "R70") (pin "1") (pinfunction "1_1") (pintype "passive"))
      (node (ref "TP3") (pin "1") (pintype "passive"))
      (node (ref "U9") (pin "5") (pinfunction "OUT_5") (pintype "passive"))
    )
    (net (code "20") (name "2V8") (class "Default")
      (node (ref "C31") (pin "2") (pinfunction "2_2") (pintype "passive"))
      (node (ref "TP2") (pin "1") (pintype "passive"))
      (node (ref "U7") (pin "5") (pinfunction "OUT_5") (pintype "passive"))
    )
    (net (code "21") (name "3V3") (class "Default")
      (node (ref "C26") (pin "2") (pinfunction "2_2") (pintype "passive"))
      (node (ref "L1") (pin "2") (pinfunction "2_2") (pintype "passive"))
      (node (ref "R59") (pin "2") (pinfunction "2_2") (pintype "passive"))
      (node (ref "TP1") (pin "1") (pintype "passive"))
      (node (ref "U6") (pin "5") (pinfunction "VOS_5") (pintype "passive"))
    )
    (net (code "22") (name "5V0") (class "Default")
      (node (ref "C163") (pin "1") (pinfunction "1_1") (pintype "passive"))
      (node (ref "C164") (pin "2") (pinfunction "2_2") (pintype "passive"))
      (node (ref "C165") (pin "2") (pinfunction "2_2") (pintype "passive"))
      (node (ref "D4") (pin "1") (pinfunction "K_1") (pintype "passive"))
      (node (ref "R62") (pin "2") (pinfunction "2_2") (pintype "passive"))
      (node (ref "TP32") (pin "1") (pintype "passive"))
    )
    (net (code "23") (name "11V") (class "Default")
      (node (ref "C41") (pin "1") (pinfunction "1_1") (pintype "passive"))
      (node (ref "C42") (pin "2") (pinfunction "2_2") (pintype "passive"))
      (node (ref "C43") (pin "2") (pinfunction "2_2") (pintype "passive"))
      (node (ref "D7") (pin "1") (pinfunction "K_1") (pintype "passive"))
      (node (ref "R53") (pin "2") (pinfunction "2_2") (pintype "passive"))
      (node (ref "TP29") (pin "1") (pintype "passive"))
    )
    (net (code "24") (name "BB_SYS") (class "Default")
      (node (ref "C166") (pin "2") (pinfunction "2_2") (pintype "passive"))
      (node (ref "C180") (pin "2") (pinfunction "2_2") (pintype "passive"))
      (node (ref "C181") (pin "2") (pinfunction "2_2") (pintype "passive"))
      (node (ref "C25") (pin "2") (pinfunction "2_2") (pintype "passive"))
      (node (ref "C27") (pin "1") (pinfunction "1_1") (pintype "passive"))
      (node (ref "C28") (pin "2") (pinfunction "2_2") (pintype "passive"))
      (node (ref "C29") (pin "2") (pinfunction "2_2") (pintype "passive"))
      (node (ref "C30") (pin "2") (pinfunction "2_2") (pintype "passive"))
      (node (ref "C35") (pin "2") (pinfunction "2_2") (pintype "passive"))
      (node (ref "C38") (pin "2") (pinfunction "2_2") (pintype "passive"))
      (node (ref "C39") (pin "2") (pinfunction "2_2") (pintype "passive"))
      (node (ref "C44") (pin "2") (pinfunction "2_2") (pintype "passive"))
      (node (ref "L10") (pin "1") (pinfunction "1_1") (pintype "passive"))
      (node (ref "L3") (pin "1") (pinfunction "1_1") (pintype "passive"))
      (node (ref "Q2") (pin "1") (pinfunction "D_1") (pintype "passive"))
      (node (ref "Q2") (pin "2") (pinfunction "D_2") (pintype "passive"))
      (node (ref "Q2") (pin "5") (pinfunction "D_5") (pintype "passive"))
      (node (ref "Q2") (pin "6") (pinfunction "D_6") (pintype "passive"))
      (node (ref "R196") (pin "2") (pinfunction "2_2") (pintype "passive"))
      (node (ref "R58") (pin "2") (pinfunction "2_2") (pintype "passive"))
      (node (ref "R61") (pin "2") (pinfunction "2_2") (pintype "passive"))
      (node (ref "R63") (pin "2") (pinfunction "2_2") (pintype "passive"))
      (node (ref "R76") (pin "2") (pinfunction "2_2") (pintype "passive"))
      (node (ref "TP31") (pin "1") (pintype "passive"))
      (node (ref "U10") (pin "3") (pinfunction "EN1_3") (pintype "passive"))
      (node (ref "U10") (pin "5") (pinfunction "EN2_5") (pintype "passive"))
      (node (ref "U10") (pin "6") (pinfunction "IN2_6") (pintype "passive"))
      (node (ref "U10") (pin "9") (pinfunction "IN1_9") (pintype "passive"))
      (node (ref "U11") (pin "2") (pinfunction "VIN_2") (pintype "power_in"))
      (node (ref "U24") (pin "2") (pinfunction "VIN_2") (pintype "power_in"))
      (node (ref "U6") (pin "1") (pinfunction "EN_1") (pintype "passive"))
      (node (ref "U6") (pin "8") (pinfunction "VIN_8") (pintype "passive"))
      (node (ref "U7") (pin "1") (pinfunction "IN_1") (pintype "passive"))
      (node (ref "U7") (pin "3") (pinfunction "EN_3") (pintype "passive"))
      (node (ref "U9") (pin "1") (pinfunction "IN_1") (pintype "passive"))
      (node (ref "U9") (pin "3") (pinfunction "EN_3") (pintype "passive"))
    )
    (net (code "25") (name "BMC_SYS") (class "Default")
      (node (ref "C116") (pin "2") (pinfunction "2_2") (pintype "passive"))
      (node (ref "C117") (pin "2") (pinfunction "2_2") (pintype "passive"))
      (node (ref "C23") (pin "1") (pinfunction "1_1") (pintype "passive"))
      (node (ref "C24") (pin "2") (pinfunction "2_2") (pintype "passive"))
      (node (ref "C32") (pin "2") (pinfunction "2_2") (pintype "passive"))
      (node (ref "C40") (pin "2") (pinfunction "2_2") (pintype "passive"))
      (node (ref "C58") (pin "2") (pinfunction "2_2") (pintype "passive"))
      (node (ref "L2") (pin "2") (pinfunction "2_2") (pintype "passive"))
      (node (ref "Q1") (pin "1") (pinfunction "D_1") (pintype "passive"))
      (node (ref "Q1") (pin "2") (pinfunction "D_2") (pintype "passive"))
      (node (ref "Q1") (pin "5") (pinfunction "D_5") (pintype "passive"))
      (node (ref "Q1") (pin "6") (pinfunction "D_6") (pintype "passive"))
      (node (ref "R189") (pin "1") (pinfunction "1_1") (pintype "passive"))
      (node (ref "R193") (pin "1") (pinfunction "1_1") (pintype "passive"))
      (node (ref "R3") (pin "2") (pinfunction "2_2") (pintype "passive"))
      (node (ref "R68") (pin "1") (pinfunction "1_1") (pintype "passive"))
      (node (ref "R74") (pin "1") (pinfunction "1_1") (pintype "passive"))
      (node (ref "TP30") (pin "1") (pintype "passive"))
      (node (ref "U8") (pin "15") (pinfunction "SYS1_15") (pintype "passive"))
      (node (ref "U8") (pin "16") (pinfunction "SYS2_16") (pintype "passive"))
    )
    (net (code "26") (name "GND") (class "Default")
      (node (ref "B2") (pin "3") (pinfunction "GND_3") (pintype "passive"))
      (node (ref "B2") (pin "4") (pinfunction "GND_4") (pintype "passive"))
      (node (ref "C116") (pin "1") (pinfunction "1_1") (pintype "passive"))
      (node (ref "C117") (pin "1") (pinfunction "1_1") (pintype "passive"))
      (node (ref "C119") (pin "1") (pinfunction "1_1") (pintype "passive"))
      (node (ref "C120") (pin "1") (pinfunction "1_1") (pintype "passive"))
      (node (ref "C139") (pin "2") (pinfunction "2_2") (pintype "passive"))
      (node (ref "C140") (pin "1") (pinfunction "1_1") (pintype "passive"))
      (node (ref "C141") (pin "2") (pinfunction "2_2") (pintype "passive"))
      (node (ref "C142") (pin "2") (pinfunction "2_2") (pintype "passive"))
      (node (ref "C161") (pin "1") (pinfunction "1_1") (pintype "passive"))
      (node (ref "C162") (pin "2") (pinfunction "2_2") (pintype "passive"))
      (node (ref "C164") (pin "1") (pinfunction "1_1") (pintype "passive"))
      (node (ref "C165") (pin "1") (pinfunction "1_1") (pintype "passive"))
      (node (ref "C166") (pin "1") (pinfunction "1_1") (pintype "passive"))
      (node (ref "C180") (pin "1") (pinfunction "1_1") (pintype "passive"))
      (node (ref "C181") (pin "1") (pinfunction "1_1") (pintype "passive"))
      (node (ref "C23") (pin "2") (pinfunction "2_2") (pintype "passive"))
      (node (ref "C24") (pin "1") (pinfunction "1_1") (pintype "passive"))
      (node (ref "C25") (pin "1") (pinfunction "1_1") (pintype "passive"))
      (node (ref "C26") (pin "1") (pinfunction "1_1") (pintype "passive"))
      (node (ref "C27") (pin "2") (pinfunction "2_2") (pintype "passive"))
      (node (ref "C28") (pin "1") (pinfunction "1_1") (pintype "passive"))
      (node (ref "C29") (pin "1") (pinfunction "1_1") (pintype "passive"))
      (node (ref "C30") (pin "1") (pinfunction "1_1") (pintype "passive"))
      (node (ref "C31") (pin "1") (pinfunction "1_1") (pintype "passive"))
      (node (ref "C32") (pin "1") (pinfunction "1_1") (pintype "passive"))
      (node (ref "C33") (pin "1") (pinfunction "1_1") (pintype "passive"))
      (node (ref "C34") (pin "1") (pinfunction "1_1") (pintype "passive"))
      (node (ref "C35") (pin "1") (pinfunction "1_1") (pintype "passive"))
      (node (ref "C36") (pin "1") (pinfunction "1_1") (pintype "passive"))
      (node (ref "C37") (pin "2") (pinfunction "2_2") (pintype "passive"))
      (node (ref "C38") (pin "1") (pinfunction "1_1") (pintype "passive"))
      (node (ref "C39") (pin "1") (pinfunction "1_1") (pintype "passive"))
      (node (ref "C40") (pin "1") (pinfunction "1_1") (pintype "passive"))
      (node (ref "C42") (pin "1") (pinfunction "1_1") (pintype "passive"))
      (node (ref "C43") (pin "1") (pinfunction "1_1") (pintype "passive"))
      (node (ref "C44") (pin "1") (pinfunction "1_1") (pintype "passive"))
      (node (ref "C58") (pin "1") (pinfunction "1_1") (pintype "passive"))
      (node (ref "D1") (pin "1") (pinfunction "C_1") (pintype "passive"))
      (node (ref "D8") (pin "1") (pinfunction "C_1") (pintype "passive"))
      (node (ref "J2") (pin "3") (pinfunction "3_3") (pintype "passive"))
      (node (ref "J2") (pin "MP1") (pinfunction "MP1_MP1") (pintype "passive"))
      (node (ref "J2") (pin "MP2") (pinfunction "MP2_MP2") (pintype "passive"))
      (node (ref "M3") (pin "2") (pinfunction "Source_2") (pintype "passive"))
      (node (ref "M4") (pin "2") (pinfunction "Source_2") (pintype "passive"))
      (node (ref "R167") (pin "1") (pinfunction "1_1") (pintype "passive"))
      (node (ref "R188") (pin "1") (pinfunction "1_1") (pintype "passive"))
      (node (ref "R190") (pin "1") (pinfunction "1_1") (pintype "passive"))
      (node (ref "R191") (pin "1") (pinfunction "1_1") (pintype "passive"))
      (node (ref "R192") (pin "1") (pinfunction "1_1") (pintype "passive"))
      (node (ref "R194") (pin "1") (pinfunction "1_1") (pintype "passive"))
      (node (ref "R195") (pin "1") (pinfunction "1_1") (pintype "passive"))
      (node (ref "R197") (pin "1") (pinfunction "1_1") (pintype "passive"))
      (node (ref "R56") (pin "1") (pinfunction "1_1") (pintype "passive"))
      (node (ref "R60") (pin "1") (pinfunction "1_1") (pintype "passive"))
      (node (ref "R65") (pin "1") (pinfunction "1_1") (pintype "passive"))
      (node (ref "R66") (pin "1") (pinfunction "1_1") (pintype "passive"))
      (node (ref "R69") (pin "2") (pinfunction "2_2") (pintype "passive"))
      (node (ref "R72") (pin "1") (pinfunction "1_1") (pintype "passive"))
      (node (ref "R91") (pin "1") (pinfunction "1_1") (pintype "passive"))
      (node (ref "U10") (pin "11") (pinfunction "EPAD_11") (pintype "passive"))
      (node (ref "U10") (pin "2") (pinfunction "GND_2") (pintype "passive"))
      (node (ref "U10") (pin "4") (pinfunction "GND_4") (pintype "passive"))
      (node (ref "U11") (pin "1") (pinfunction "PGND_1") (pintype "power_in"))
      (node (ref "U11") (pin "5") (pinfunction "AGND_5") (pintype "power_in"))
      (node (ref "U11") (pin "7") (pinfunction "DAP_7") (pintype "power_in"))
      (node (ref "U18") (pin "11") (pinfunction "NC_11") (pintype "passive"))
      (node (ref "U18") (pin "13") (pinfunction "EP_13") (pintype "passive"))
      (node (ref "U18") (pin "3") (pinfunction "VSS_3") (pintype "power_in"))
      (node (ref "U18") (pin "4") (pinfunction "NC_4") (pintype "passive"))
      (node (ref "U18") (pin "9") (pinfunction "NC_9") (pintype "passive"))
      (node (ref "U24") (pin "1") (pinfunction "PGND_1") (pintype "power_in"))
      (node (ref "U24") (pin "5") (pinfunction "AGND_5") (pintype "power_in"))
      (node (ref "U24") (pin "7") (pinfunction "DAP_7") (pintype "power_in"))
      (node (ref "U5") (pin "2") (pinfunction "GND_2") (pintype "power_in"))
      (node (ref "U6") (pin "2") (pinfunction "GND_2") (pintype "passive"))
      (node (ref "U6") (pin "3") (pinfunction "GND_3") (pintype "passive"))
      (node (ref "U6") (pin "9") (pinfunction "EP_9") (pintype "passive"))
      (node (ref "U7") (pin "2") (pinfunction "GND_2") (pintype "passive"))
      (node (ref "U8") (pin "17") (pinfunction "PGND1_17") (pintype "passive"))
      (node (ref "U8") (pin "18") (pinfunction "PGND2_18") (pintype "passive"))
      (node (ref "U8") (pin "25") (pinfunction "THERMAL_PAD_25") (pintype "passive"))
      (node (ref "U9") (pin "2") (pinfunction "GND_2") (pintype "passive"))
    )
    (net (code "27") (name "Net-(D1-A)") (class "Default")
      (node (ref "D1") (pin "2") (pinfunction "A_2") (pintype "passive"))
      (node (ref "R3") (pin "1") (pinfunction "1_1") (pintype "passive"))
    )
    (net (code "28") (name "Net-(D3-A)") (class "Default")
      (node (ref "D3") (pin "2") (pinfunction "A_2") (pintype "passive"))
      (node (ref "R68") (pin "2") (pinfunction "2_2") (pintype "passive"))
    )
    (net (code "29") (name "Net-(D3-C)") (class "Default")
      (node (ref "D3") (pin "1") (pinfunction "C_1") (pintype "passive"))
      (node (ref "U8") (pin "3") (pinfunction "~{PG}_3") (pintype "passive"))
    )
    (net (code "30") (name "Net-(D4-A)") (class "Default")
      (node (ref "D4") (pin "2") (pinfunction "A_2") (pintype "passive"))
      (node (ref "L10") (pin "2") (pinfunction "2_2") (pintype "passive"))
      (node (ref "U24") (pin "6") (pinfunction "SW_6") (pintype "power_in"))
    )
    (net (code "31") (name "Net-(D6-A)") (class "Default")
      (node (ref "D6") (pin "2") (pinfunction "A_2") (pintype "passive"))
      (node (ref "R74") (pin "2") (pinfunction "2_2") (pintype "passive"))
    )
    (net (code "32") (name "Net-(D6-C)") (class "Default")
      (node (ref "D6") (pin "1") (pinfunction "C_1") (pintype "passive"))
      (node (ref "U8") (pin "4") (pinfunction "STAT_4") (pintype "passive"))
    )
    (net (code "33") (name "Net-(D7-A)") (class "Default")
      (node (ref "D7") (pin "2") (pinfunction "A_2") (pintype "passive"))
      (node (ref "L3") (pin "2") (pinfunction "2_2") (pintype "passive"))
      (node (ref "U11") (pin "6") (pinfunction "SW_6") (pintype "power_in"))
    )
    (net (code "34") (name "Net-(D8-A)") (class "Default")
      (node (ref "D8") (pin "2") (pinfunction "A_2") (pintype "passive"))
      (node (ref "R196") (pin "1") (pinfunction "1_1") (pintype "passive"))
    )
    (net (code "35") (name "Net-(M3-Drain)") (class "Default")
      (node (ref "M3") (pin "3") (pinfunction "Drain_3") (pintype "passive"))
      (node (ref "Q1") (pin "3") (pinfunction "G_3") (pintype "passive"))
      (node (ref "Q2") (pin "3") (pinfunction "G_3") (pintype "passive"))
      (node (ref "R57") (pin "2") (pinfunction "2_2") (pintype "passive"))
    )
    (net (code "36") (name "Net-(M3-Gate)") (class "Default")
      (node (ref "M3") (pin "1") (pinfunction "Gate_1") (pintype "passive"))
      (node (ref "R66") (pin "2") (pinfunction "2_2") (pintype "passive"))
      (node (ref "U5") (pin "4") (pinfunction "OUT_4") (pintype "output"))
    )
    (net (code "37") (name "Net-(M4-Drain)") (class "Default")
      (node (ref "M4") (pin "3") (pinfunction "Drain_3") (pintype "passive"))
      (node (ref "R61") (pin "1") (pinfunction "1_1") (pintype "passive"))
      (node (ref "U5") (pin "6") (pinfunction "~{CLR}_6") (pintype "input"))
    )
    (net (code "38") (name "Net-(Q1-S)") (class "Default")
      (node (ref "Q1") (pin "4") (pinfunction "S_4") (pintype "passive"))
      (node (ref "Q2") (pin "4") (pinfunction "S_4") (pintype "passive"))
      (node (ref "R57") (pin "1") (pinfunction "1_1") (pintype "passive"))
    )
    (net (code "39") (name "Net-(U5-~{PB_IN})") (class "Default")
      (node (ref "B2") (pin "1") (pinfunction "GND_1") (pintype "passive"))
      (node (ref "B2") (pin "2") (pinfunction "GND_2") (pintype "passive"))
      (node (ref "U5") (pin "1") (pinfunction "~{PB_IN}_1") (pintype "input"))
    )
    (net (code "40") (name "Net-(U6-FB)") (class "Default")
      (node (ref "R59") (pin "1") (pinfunction "1_1") (pintype "passive"))
      (node (ref "R60") (pin "2") (pinfunction "2_2") (pintype "passive"))
      (node (ref "U6") (pin "4") (pinfunction "FB_4") (pintype "passive"))
    )
    (net (code "41") (name "Net-(U6-SW)") (class "Default")
      (node (ref "L1") (pin "1") (pinfunction "1_1") (pintype "passive"))
      (node (ref "U6") (pin "7") (pinfunction "SW_7") (pintype "passive"))
    )
    (net (code "42") (name "Net-(U8-BTST)") (class "Default")
      (node (ref "C118") (pin "1") (pinfunction "1_1") (pintype "passive"))
      (node (ref "U8") (pin "21") (pinfunction "BTST_21") (pintype "passive"))
    )
    (net (code "43") (name "Net-(U8-ILIM)") (class "Default")
      (node (ref "R190") (pin "2") (pinfunction "2_2") (pintype "passive"))
      (node (ref "U8") (pin "10") (pinfunction "ILIM_10") (pintype "passive"))
    )
    (net (code "44") (name "Net-(U8-PMID)") (class "Default")
      (node (ref "C162") (pin "1") (pinfunction "1_1") (pintype "passive"))
      (node (ref "U8") (pin "23") (pinfunction "PMID_23") (pintype "passive"))
    )
    (net (code "45") (name "Net-(U8-SW1)") (class "Default")
      (node (ref "C118") (pin "2") (pinfunction "2_2") (pintype "passive"))
      (node (ref "L2") (pin "1") (pinfunction "1_1") (pintype "passive"))
      (node (ref "U8") (pin "19") (pinfunction "SW1_19") (pintype "passive"))
      (node (ref "U8") (pin "20") (pinfunction "SW2_20") (pintype "passive"))
    )
    (net (code "46") (name "Net-(U10-FB1)") (class "Default")
      (node (ref "R64") (pin "1") (pinfunction "1_1") (pintype "passive"))
      (node (ref "R65") (pin "2") (pinfunction "2_2") (pintype "passive"))
      (node (ref "U10") (pin "1") (pinfunction "FB1_1") (pintype "passive"))
    )
    (net (code "47") (name "Net-(U10-FB2)") (class "Default")
      (node (ref "R67") (pin "2") (pinfunction "2_2") (pintype "passive"))
      (node (ref "R69") (pin "1") (pinfunction "1_1") (pintype "passive"))
      (node (ref "U10") (pin "7") (pinfunction "FB2_7") (pintype "passive"))
    )
    (net (code "48") (name "Net-(U11-EN)") (class "Default")
      (node (ref "R76") (pin "1") (pinfunction "1_1") (pintype "passive"))
      (node (ref "U11") (pin "3") (pinfunction "EN_3") (pintype "input"))
    )
    (net (code "49") (name "Net-(U11-FB)") (class "Default")
      (node (ref "C41") (pin "2") (pinfunction "2_2") (pintype "passive"))
      (node (ref "R53") (pin "1") (pinfunction "1_1") (pintype "passive"))
      (node (ref "R56") (pin "2") (pinfunction "2_2") (pintype "passive"))
      (node (ref "U11") (pin "4") (pinfunction "FB_4") (pintype "input"))
    )
    (net (code "50") (name "Net-(U18-BIN)") (class "Default")
      (node (ref "R197") (pin "2") (pinfunction "2_2") (pintype "passive"))
      (node (ref "U18") (pin "10") (pinfunction "BIN_10") (pintype "input"))
    )
    (net (code "51") (name "Net-(U18-SRP)") (class "Default")
      (node (ref "J2") (pin "1") (pinfunction "1_1") (pintype "passive"))
      (node (ref "R71") (pin "2") (pinfunction "2_2") (pintype "passive"))
      (node (ref "U18") (pin "8") (pinfunction "SRP_8") (pintype "passive"))
    )
    (net (code "52") (name "Net-(U18-VDD)") (class "Default")
      (node (ref "C141") (pin "1") (pinfunction "1_1") (pintype "passive"))
      (node (ref "U18") (pin "5") (pinfunction "VDD_5") (pintype "power_in"))
    )
    (net (code "53") (name "Net-(U24-EN)") (class "Default")
      (node (ref "R63") (pin "1") (pinfunction "1_1") (pintype "passive"))
      (node (ref "U24") (pin "3") (pinfunction "EN_3") (pintype "input"))
    )
    (net (code "54") (name "Net-(U24-FB)") (class "Default")
      (node (ref "C163") (pin "2") (pinfunction "2_2") (pintype "passive"))
      (node (ref "R62") (pin "1") (pinfunction "1_1") (pintype "passive"))
      (node (ref "R72") (pin "2") (pinfunction "2_2") (pintype "passive"))
      (node (ref "U24") (pin "4") (pinfunction "FB_4") (pintype "input"))
    )
    (net (code "55") (name "P_VBUS") (class "Default")
      (node (ref "C139") (pin "1") (pinfunction "1_1") (pintype "passive"))
      (node (ref "U8") (pin "1") (pinfunction "VBUS1_1") (pintype "passive"))
      (node (ref "U8") (pin "24") (pinfunction "VBUS2_24") (pintype "passive"))
    )
    (net (code "56") (name "VBAT") (class "Default")
      (node (ref "C140") (pin "2") (pinfunction "2_2") (pintype "passive"))
      (node (ref "C142") (pin "1") (pinfunction "1_1") (pintype "passive"))
      (node (ref "C33") (pin "2") (pinfunction "2_2") (pintype "passive"))
      (node (ref "C34") (pin "2") (pinfunction "2_2") (pintype "passive"))
      (node (ref "C37") (pin "1") (pinfunction "1_1") (pintype "passive"))
      (node (ref "R71") (pin "1") (pinfunction "1_1") (pintype "passive"))
      (node (ref "TP35") (pin "1") (pintype "passive"))
      (node (ref "U18") (pin "6") (pinfunction "BAT_6") (pintype "passive"))
      (node (ref "U18") (pin "7") (pinfunction "SRN_7") (pintype "passive"))
      (node (ref "U5") (pin "3") (pinfunction "VCC_3") (pintype "power_in"))
      (node (ref "U8") (pin "13") (pinfunction "BAT1_13") (pintype "passive"))
      (node (ref "U8") (pin "14") (pinfunction "BAT2_14") (pintype "passive"))
    )
    (net (code "57") (name "unconnected-(U6-PG-Pad6)") (class "Default")
      (node (ref "U6") (pin "6") (pinfunction "PG_6") (pintype "passive"))
    )
    (net (code "58") (name "unconnected-(U7-NC-Pad4)") (class "Default")
      (node (ref "U7") (pin "4") (pinfunction "NC_4") (pintype "passive"))
    )
    (net (code "59") (name "unconnected-(U9-NC-Pad4)") (class "Default")
      (node (ref "U9") (pin "4") (pinfunction "NC_4") (pintype "passive+no_connect"))
    )
  )
)
